# esphome-lg-pqrcuds0-rev2.net
KiCad netlist of a schematic drawn in EAGLE
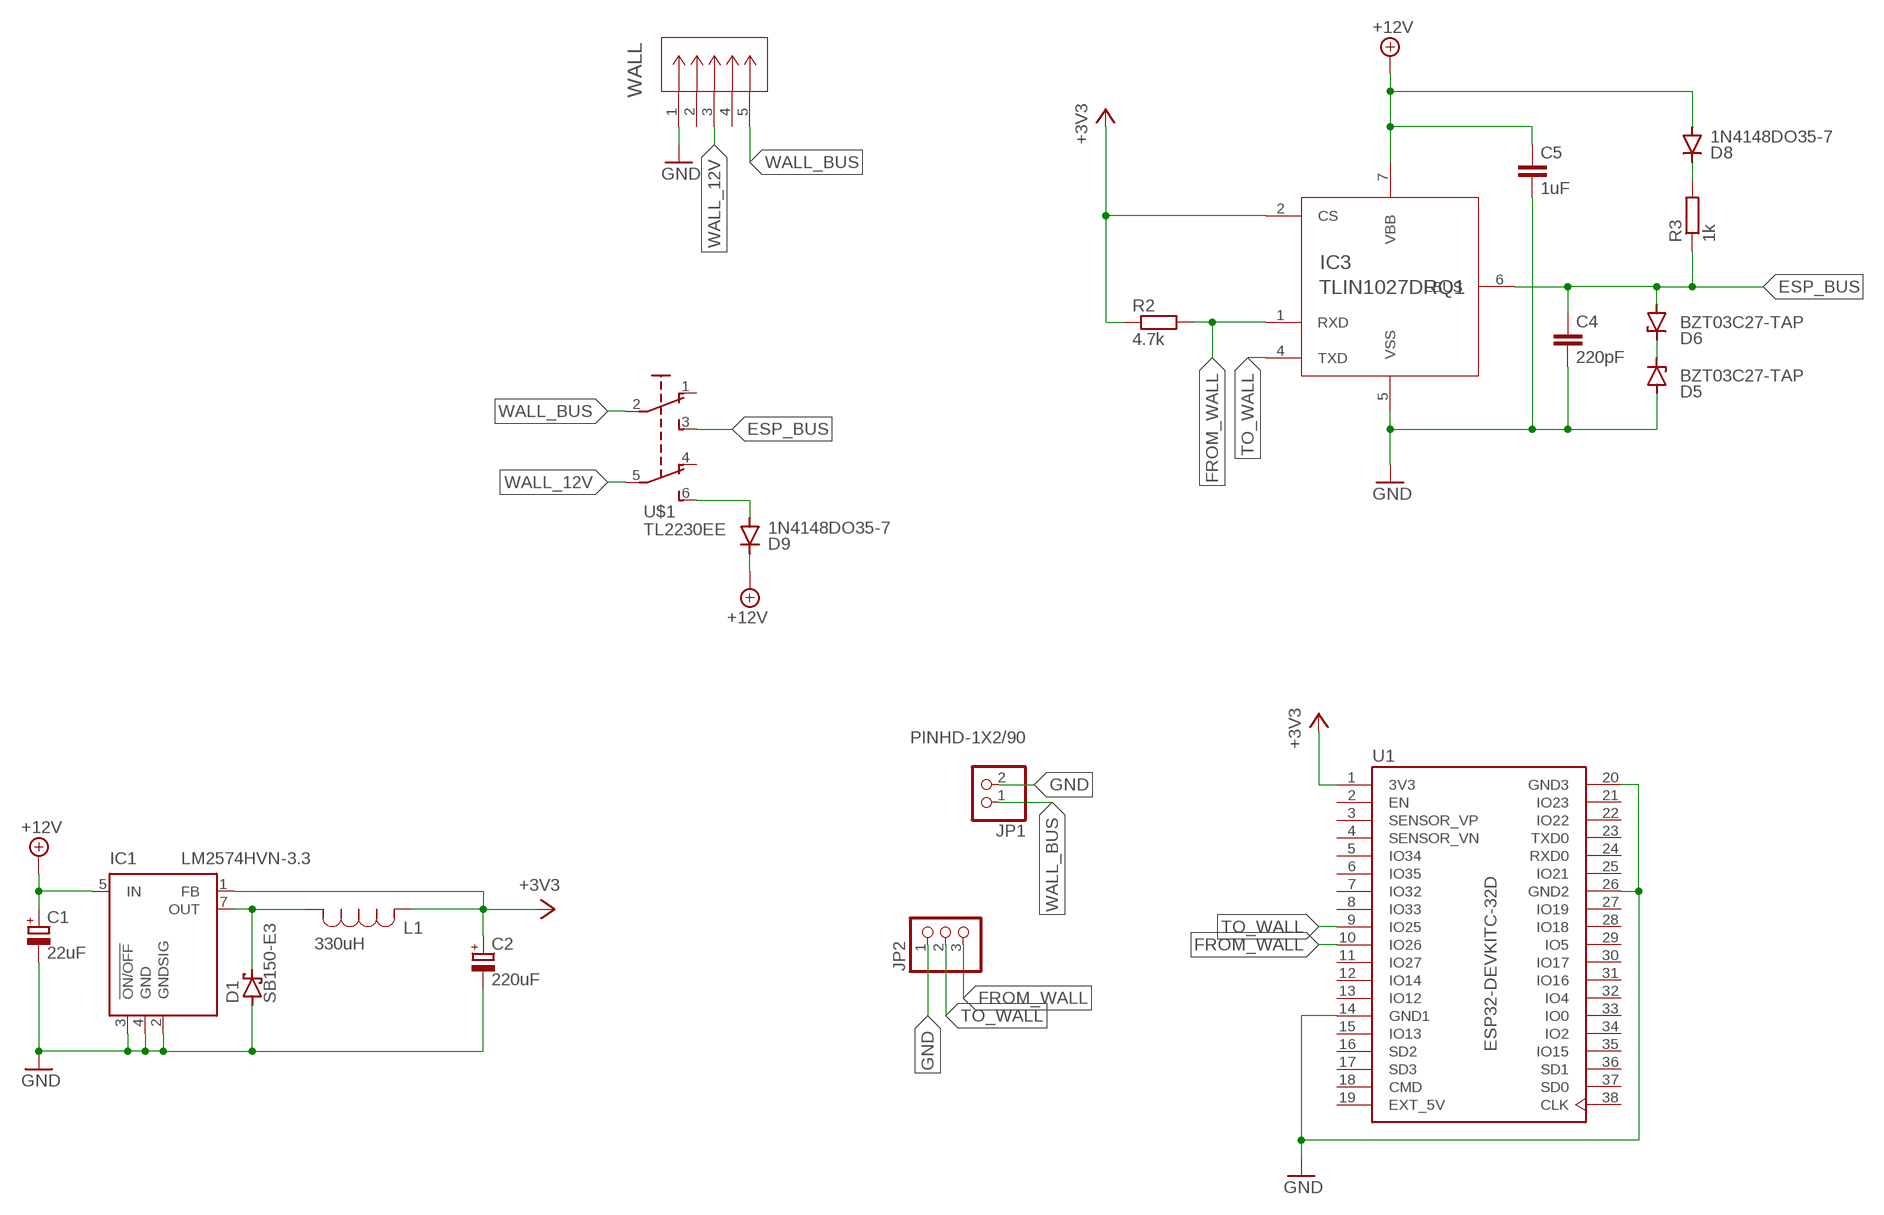
[diagram p0: schematic, sheet 1]

(export (version "E")
  (design (tool "Eeschema 10.0.6"))
  (components
    (comp (ref "C1")
      (value "22uF")
      (footprint "eagle-import:E2,5-6")
      (libsource (lib "eagle-import") (part "CPOL-EUE2.5-6"))
    )
    (comp (ref "C2")
      (value "220uF")
      (footprint "eagle-import:E2,5-6E")
      (libsource (lib "eagle-import") (part "CPOL-EUE2,5-6E"))
    )
    (comp (ref "C4")
      (value "220pF")
      (footprint "eagle-import:C050-025X075")
      (libsource (lib "eagle-import") (part "C-EU050-025X075"))
    )
    (comp (ref "C5")
      (value "1uF")
      (footprint "eagle-import:C050-025X075")
      (libsource (lib "eagle-import") (part "C-EU050-025X075"))
    )
    (comp (ref "D1")
      (value "SB150-E3")
      (footprint "eagle-import:DO35-7")
      (libsource (lib "eagle-import") (part "SCHOTTKY-DIODEDO35-7"))
    )
    (comp (ref "D5")
      (value "BZT03C27-TAP")
      (footprint "eagle-import:SOD57Z10")
      (libsource (lib "eagle-import") (part "ZENER-DIODESOD57-10"))
    )
    (comp (ref "D6")
      (value "BZT03C27-TAP")
      (footprint "eagle-import:SOD57Z10")
      (libsource (lib "eagle-import") (part "ZENER-DIODESOD57-10"))
    )
    (comp (ref "D8")
      (value "1N4148DO35-7")
      (footprint "eagle-import:DO35-7")
      (libsource (lib "eagle-import") (part "1N4148DO35-7"))
    )
    (comp (ref "D9")
      (value "1N4148DO35-7")
      (footprint "eagle-import:DO35-7")
      (libsource (lib "eagle-import") (part "1N4148DO35-7"))
    )
    (comp (ref "IC1")
      (value "LM2574HVN-3.3")
      (footprint "eagle-import:DIL08")
      (libsource (lib "eagle-import") (part "LM2574?-HVN3.3"))
    )
    (comp (ref "IC3")
      (value "TLIN1027DRQ1")
      (footprint "eagle-import:SOIC8")
      (libsource (lib "eagle-import") (part "TLIN1027DRQ1"))
    )
    (comp (ref "JP1")
      (value "PINHD-1X2/90")
      (footprint "eagle-import:1X02_90")
      (libsource (lib "eagle-import") (part "PINHD-1X2/90"))
    )
    (comp (ref "JP2")
      (value "PINHD-1X3/90")
      (footprint "eagle-import:1X03_90")
      (libsource (lib "eagle-import") (part "PINHD-1X3/90"))
    )
    (comp (ref "L1")
      (value "330uH")
      (footprint "eagle-import:AIAP-02_ABR")
      (fields (field (name "MANUFACTURER_PART_NUMBER") "AIAP-02-331K"))
      (libsource (lib "eagle-import") (part "AIAP-02-331K"))
    )
    (comp (ref "R2")
      (value "4.7k")
      (footprint "eagle-import:0204_7")
      (libsource (lib "eagle-import") (part "R-EU_0204/7"))
    )
    (comp (ref "R3")
      (value "1k")
      (footprint "eagle-import:0204_7")
      (libsource (lib "eagle-import") (part "R-EU_0204/7"))
    )
    (comp (ref "U$1")
      (value "TL2230EE")
      (footprint "eagle-import:TL2230")
      (libsource (lib "eagle-import") (part "TL2230EE"))
    )
    (comp (ref "U1")
      (value "ESP32-DEVKITC-32D")
      (footprint "eagle-import:MODULE_ESP32-DEVKITC-32D")
      (fields (field (name "MF") "Espressif Systems"))
      (libsource (lib "eagle-import") (part "ESP32-DEVKITC-32D"))
    )
    (comp (ref "WALL")
      (value "S5B-ZR(LF)(SN)")
      (footprint "eagle-import:CONN_S5B-ZR_JST")
      (fields (field (name "COPYRIGHT") "Copyright (C) 2018 Accelerated Designs. All rights reserved"))
      (libsource (lib "eagle-import") (part "S5B-ZR(LF)(SN)"))
    )
  )
  (nets
    (net (code "1") (name "+3V3") (class "Default")
      (node (ref "C2") (pin "+") (pinfunction "+_+") (pintype "passive"))
      (node (ref "IC1") (pin "1") (pinfunction "FB_1") (pintype "input"))
      (node (ref "IC3") (pin "2") (pinfunction "CS_2") (pintype "input"))
      (node (ref "L1") (pin "2") (pinfunction "2_2") (pintype "passive"))
      (node (ref "R2") (pin "1") (pinfunction "1_1") (pintype "passive"))
      (node (ref "U1") (pin "1") (pinfunction "3V3_1") (pintype "power_in"))
    )
    (net (code "2") (name "+12V") (class "Default")
      (node (ref "C1") (pin "+") (pinfunction "+_+") (pintype "passive"))
      (node (ref "C5") (pin "1") (pinfunction "1_1") (pintype "passive"))
      (node (ref "D8") (pin "A") (pinfunction "A_A") (pintype "passive"))
      (node (ref "D9") (pin "C") (pinfunction "C_C") (pintype "passive"))
      (node (ref "IC1") (pin "5") (pinfunction "IN_5") (pintype "input"))
      (node (ref "IC3") (pin "7") (pinfunction "VBB_7") (pintype "power_in"))
    )
    (net (code "3") (name "/EXT_5V") (class "Default")
      (node (ref "U1") (pin "19") (pinfunction "EXT_5V_19") (pintype "power_in"))
    )
    (net (code "4") (name "ESP_BUS") (class "Default")
      (node (ref "C4") (pin "1") (pinfunction "1_1") (pintype "passive"))
      (node (ref "D6") (pin "A") (pinfunction "A_A") (pintype "passive"))
      (node (ref "IC3") (pin "6") (pinfunction "LBUS_6") (pintype "bidirectional"))
      (node (ref "R3") (pin "1") (pinfunction "1_1") (pintype "passive"))
      (node (ref "U$1") (pin "3") (pinfunction "S_3") (pintype "passive"))
    )
    (net (code "5") (name "FROM_WALL") (class "Default")
      (node (ref "IC3") (pin "1") (pinfunction "RXD_1") (pintype "output"))
      (node (ref "JP2") (pin "3") (pinfunction "3_3") (pintype "passive"))
      (node (ref "R2") (pin "2") (pinfunction "2_2") (pintype "passive"))
      (node (ref "U1") (pin "10") (pinfunction "IO26_10") (pintype "bidirectional"))
    )
    (net (code "6") (name "GND") (class "Default")
      (node (ref "C1") (pin "-") (pinfunction "-_-") (pintype "passive"))
      (node (ref "C2") (pin "-") (pinfunction "-_-") (pintype "passive"))
      (node (ref "C4") (pin "2") (pinfunction "2_2") (pintype "passive"))
      (node (ref "C5") (pin "2") (pinfunction "2_2") (pintype "passive"))
      (node (ref "D1") (pin "A") (pinfunction "A_A") (pintype "passive"))
      (node (ref "D5") (pin "A") (pinfunction "A_A") (pintype "passive"))
      (node (ref "IC1") (pin "2") (pinfunction "GNDSIG_2") (pintype "input"))
      (node (ref "IC1") (pin "3") (pinfunction "~{ON/OFF}_3") (pintype "input"))
      (node (ref "IC1") (pin "4") (pinfunction "GND_4") (pintype "power_in"))
      (node (ref "IC3") (pin "5") (pinfunction "VSS_5") (pintype "power_in"))
      (node (ref "JP1") (pin "2") (pinfunction "2_2") (pintype "passive"))
      (node (ref "JP2") (pin "1") (pinfunction "1_1") (pintype "passive"))
      (node (ref "U1") (pin "14") (pinfunction "GND1_14") (pintype "power_in"))
      (node (ref "U1") (pin "20") (pinfunction "GND3_20") (pintype "power_in"))
      (node (ref "U1") (pin "26") (pinfunction "GND2_26") (pintype "power_in"))
      (node (ref "WALL") (pin "1") (pinfunction "1_1") (pintype "passive"))
    )
    (net (code "7") (name "Net-(D5-PadC)") (class "Default")
      (node (ref "D5") (pin "C") (pinfunction "C_C") (pintype "passive"))
      (node (ref "D6") (pin "C") (pinfunction "C_C") (pintype "passive"))
    )
    (net (code "8") (name "Net-(D8-PadC)") (class "Default")
      (node (ref "D8") (pin "C") (pinfunction "C_C") (pintype "passive"))
      (node (ref "R3") (pin "2") (pinfunction "2_2") (pintype "passive"))
    )
    (net (code "9") (name "Net-(IC1-OUT)") (class "Default")
      (node (ref "D1") (pin "C") (pinfunction "C_C") (pintype "passive"))
      (node (ref "IC1") (pin "7") (pinfunction "OUT_7") (pintype "passive"))
      (node (ref "L1") (pin "1") (pinfunction "1_1") (pintype "passive"))
    )
    (net (code "10") (name "Net-(U$1-S1)") (class "Default")
      (node (ref "D9") (pin "A") (pinfunction "A_A") (pintype "passive"))
      (node (ref "U$1") (pin "6") (pinfunction "S1_6") (pintype "passive"))
    )
    (net (code "11") (name "TO_WALL") (class "Default")
      (node (ref "IC3") (pin "4") (pinfunction "TXD_4") (pintype "input"))
      (node (ref "JP2") (pin "2") (pinfunction "2_2") (pintype "passive"))
      (node (ref "U1") (pin "9") (pinfunction "IO25_9") (pintype "bidirectional"))
    )
    (net (code "12") (name "WALL_12V") (class "Default")
      (node (ref "U$1") (pin "5") (pinfunction "P1_5") (pintype "passive"))
      (node (ref "WALL") (pin "3") (pinfunction "3_3") (pintype "passive"))
    )
    (net (code "13") (name "WALL_BUS") (class "Default")
      (node (ref "JP1") (pin "1") (pinfunction "1_1") (pintype "passive"))
      (node (ref "U$1") (pin "2") (pinfunction "P_2") (pintype "passive"))
      (node (ref "WALL") (pin "5") (pinfunction "5_5") (pintype "passive"))
    )
    (net (code "14") (name "unconnected-(U$1-O-Pad1)") (class "Default")
      (node (ref "U$1") (pin "1") (pinfunction "O_1") (pintype "passive"))
    )
    (net (code "15") (name "unconnected-(U$1-O1-Pad4)") (class "Default")
      (node (ref "U$1") (pin "4") (pinfunction "O1_4") (pintype "passive"))
    )
    (net (code "16") (name "unconnected-(U1-CLK-Pad38)") (class "Default")
      (node (ref "U1") (pin "38") (pinfunction "CLK_38") (pintype "input"))
    )
    (net (code "17") (name "unconnected-(U1-CMD-Pad18)") (class "Default")
      (node (ref "U1") (pin "18") (pinfunction "CMD_18") (pintype "bidirectional"))
    )
    (net (code "18") (name "unconnected-(U1-EN-Pad2)") (class "Default")
      (node (ref "U1") (pin "2") (pinfunction "EN_2") (pintype "input"))
    )
    (net (code "19") (name "unconnected-(U1-IO0-Pad33)") (class "Default")
      (node (ref "U1") (pin "33") (pinfunction "IO0_33") (pintype "bidirectional"))
    )
    (net (code "20") (name "unconnected-(U1-IO2-Pad34)") (class "Default")
      (node (ref "U1") (pin "34") (pinfunction "IO2_34") (pintype "bidirectional"))
    )
    (net (code "21") (name "unconnected-(U1-IO4-Pad32)") (class "Default")
      (node (ref "U1") (pin "32") (pinfunction "IO4_32") (pintype "bidirectional"))
    )
    (net (code "22") (name "unconnected-(U1-IO5-Pad29)") (class "Default")
      (node (ref "U1") (pin "29") (pinfunction "IO5_29") (pintype "bidirectional"))
    )
    (net (code "23") (name "unconnected-(U1-IO12-Pad13)") (class "Default")
      (node (ref "U1") (pin "13") (pinfunction "IO12_13") (pintype "bidirectional"))
    )
    (net (code "24") (name "unconnected-(U1-IO13-Pad15)") (class "Default")
      (node (ref "U1") (pin "15") (pinfunction "IO13_15") (pintype "bidirectional"))
    )
    (net (code "25") (name "unconnected-(U1-IO14-Pad12)") (class "Default")
      (node (ref "U1") (pin "12") (pinfunction "IO14_12") (pintype "bidirectional"))
    )
    (net (code "26") (name "unconnected-(U1-IO15-Pad35)") (class "Default")
      (node (ref "U1") (pin "35") (pinfunction "IO15_35") (pintype "bidirectional"))
    )
    (net (code "27") (name "unconnected-(U1-IO16-Pad31)") (class "Default")
      (node (ref "U1") (pin "31") (pinfunction "IO16_31") (pintype "bidirectional"))
    )
    (net (code "28") (name "unconnected-(U1-IO17-Pad30)") (class "Default")
      (node (ref "U1") (pin "30") (pinfunction "IO17_30") (pintype "bidirectional"))
    )
    (net (code "29") (name "unconnected-(U1-IO18-Pad28)") (class "Default")
      (node (ref "U1") (pin "28") (pinfunction "IO18_28") (pintype "bidirectional"))
    )
    (net (code "30") (name "unconnected-(U1-IO19-Pad27)") (class "Default")
      (node (ref "U1") (pin "27") (pinfunction "IO19_27") (pintype "bidirectional"))
    )
    (net (code "31") (name "unconnected-(U1-IO21-Pad25)") (class "Default")
      (node (ref "U1") (pin "25") (pinfunction "IO21_25") (pintype "bidirectional"))
    )
    (net (code "32") (name "unconnected-(U1-IO22-Pad22)") (class "Default")
      (node (ref "U1") (pin "22") (pinfunction "IO22_22") (pintype "bidirectional"))
    )
    (net (code "33") (name "unconnected-(U1-IO23-Pad21)") (class "Default")
      (node (ref "U1") (pin "21") (pinfunction "IO23_21") (pintype "bidirectional"))
    )
    (net (code "34") (name "unconnected-(U1-IO27-Pad11)") (class "Default")
      (node (ref "U1") (pin "11") (pinfunction "IO27_11") (pintype "bidirectional"))
    )
    (net (code "35") (name "unconnected-(U1-IO32-Pad7)") (class "Default")
      (node (ref "U1") (pin "7") (pinfunction "IO32_7") (pintype "bidirectional"))
    )
    (net (code "36") (name "unconnected-(U1-IO33-Pad8)") (class "Default")
      (node (ref "U1") (pin "8") (pinfunction "IO33_8") (pintype "bidirectional"))
    )
    (net (code "37") (name "unconnected-(U1-IO34-Pad5)") (class "Default")
      (node (ref "U1") (pin "5") (pinfunction "IO34_5") (pintype "bidirectional"))
    )
    (net (code "38") (name "unconnected-(U1-IO35-Pad6)") (class "Default")
      (node (ref "U1") (pin "6") (pinfunction "IO35_6") (pintype "bidirectional"))
    )
    (net (code "39") (name "unconnected-(U1-RXD0-Pad24)") (class "Default")
      (node (ref "U1") (pin "24") (pinfunction "RXD0_24") (pintype "input"))
    )
    (net (code "40") (name "unconnected-(U1-SD0-Pad37)") (class "Default")
      (node (ref "U1") (pin "37") (pinfunction "SD0_37") (pintype "bidirectional"))
    )
    (net (code "41") (name "unconnected-(U1-SD1-Pad36)") (class "Default")
      (node (ref "U1") (pin "36") (pinfunction "SD1_36") (pintype "bidirectional"))
    )
    (net (code "42") (name "unconnected-(U1-SD2-Pad16)") (class "Default")
      (node (ref "U1") (pin "16") (pinfunction "SD2_16") (pintype "bidirectional"))
    )
    (net (code "43") (name "unconnected-(U1-SD3-Pad17)") (class "Default")
      (node (ref "U1") (pin "17") (pinfunction "SD3_17") (pintype "bidirectional"))
    )
    (net (code "44") (name "unconnected-(U1-SENSOR_VN-Pad4)") (class "Default")
      (node (ref "U1") (pin "4") (pinfunction "SENSOR_VN_4") (pintype "input"))
    )
    (net (code "45") (name "unconnected-(U1-SENSOR_VP-Pad3)") (class "Default")
      (node (ref "U1") (pin "3") (pinfunction "SENSOR_VP_3") (pintype "input"))
    )
    (net (code "46") (name "unconnected-(U1-TXD0-Pad23)") (class "Default")
      (node (ref "U1") (pin "23") (pinfunction "TXD0_23") (pintype "output"))
    )
    (net (code "47") (name "unconnected-(WALL-Pad2)") (class "Default")
      (node (ref "WALL") (pin "2") (pinfunction "2_2") (pintype "passive"))
    )
    (net (code "48") (name "unconnected-(WALL-Pad4)") (class "Default")
      (node (ref "WALL") (pin "4") (pinfunction "4_4") (pintype "passive"))
    )
  )
)
